# SCH_TSIB_v1_2022-11-26.net
KiCad netlist of a schematic drawn in EasyEDA
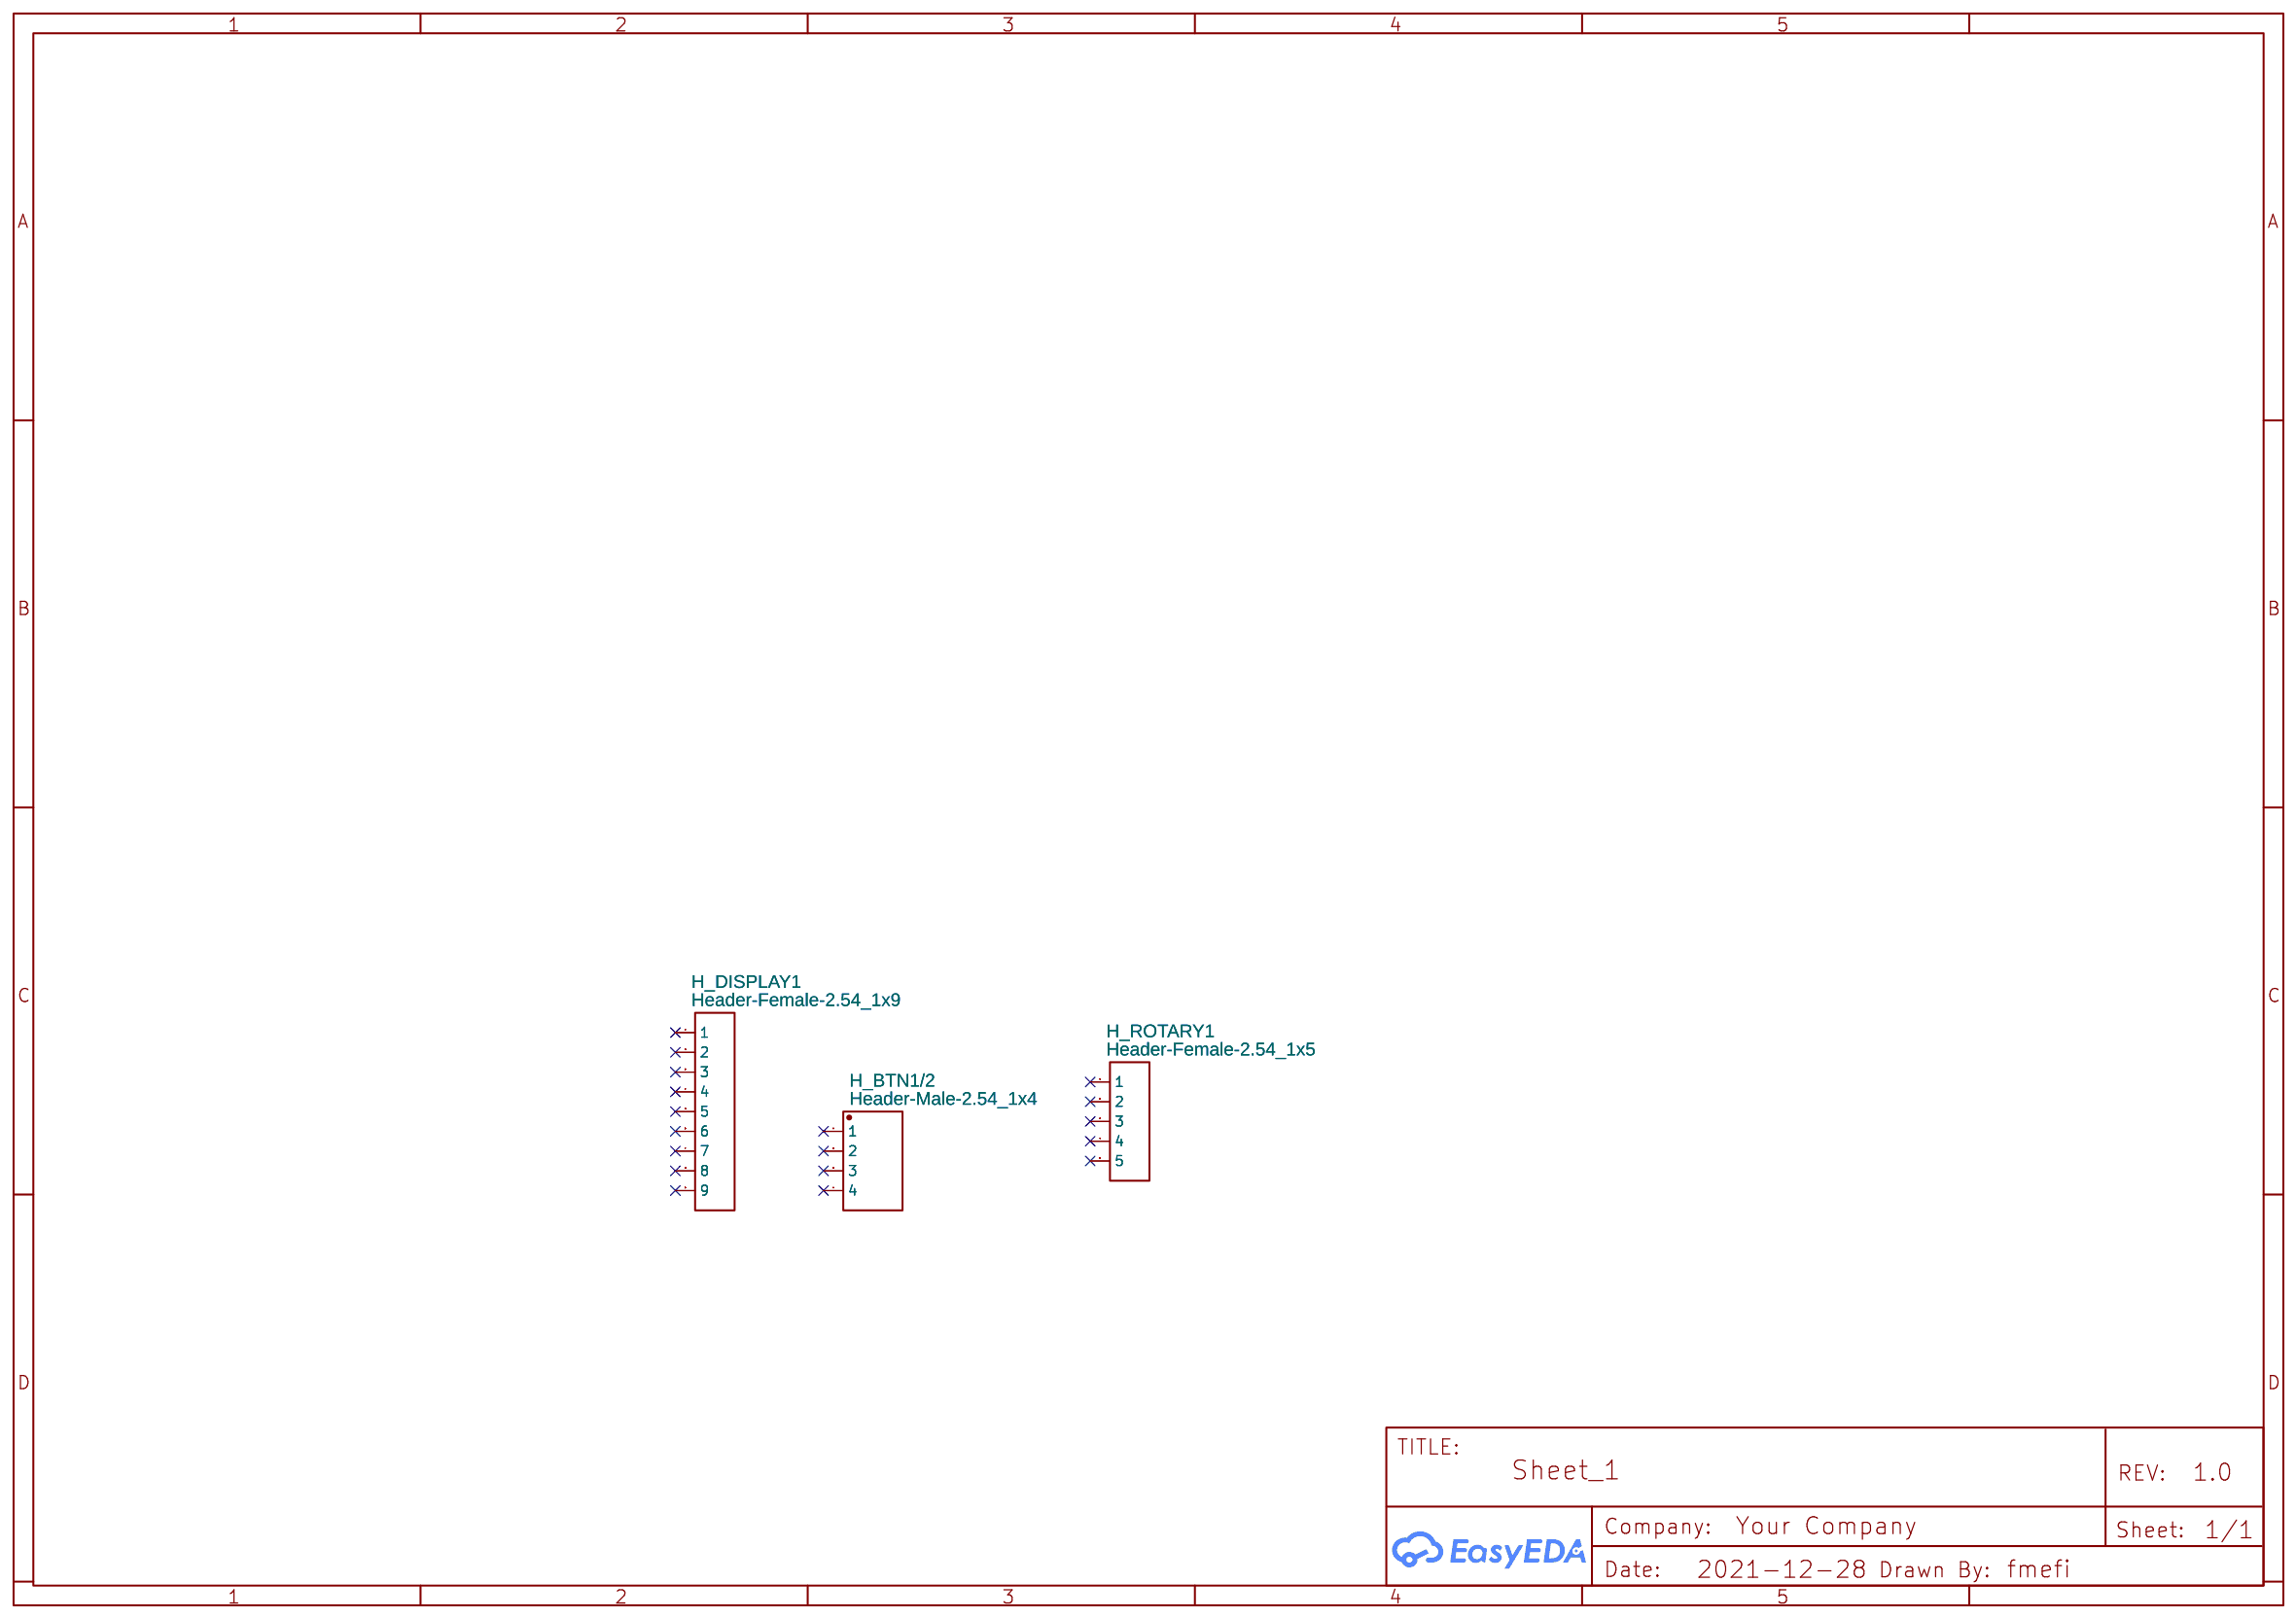
[diagram p0: UX]
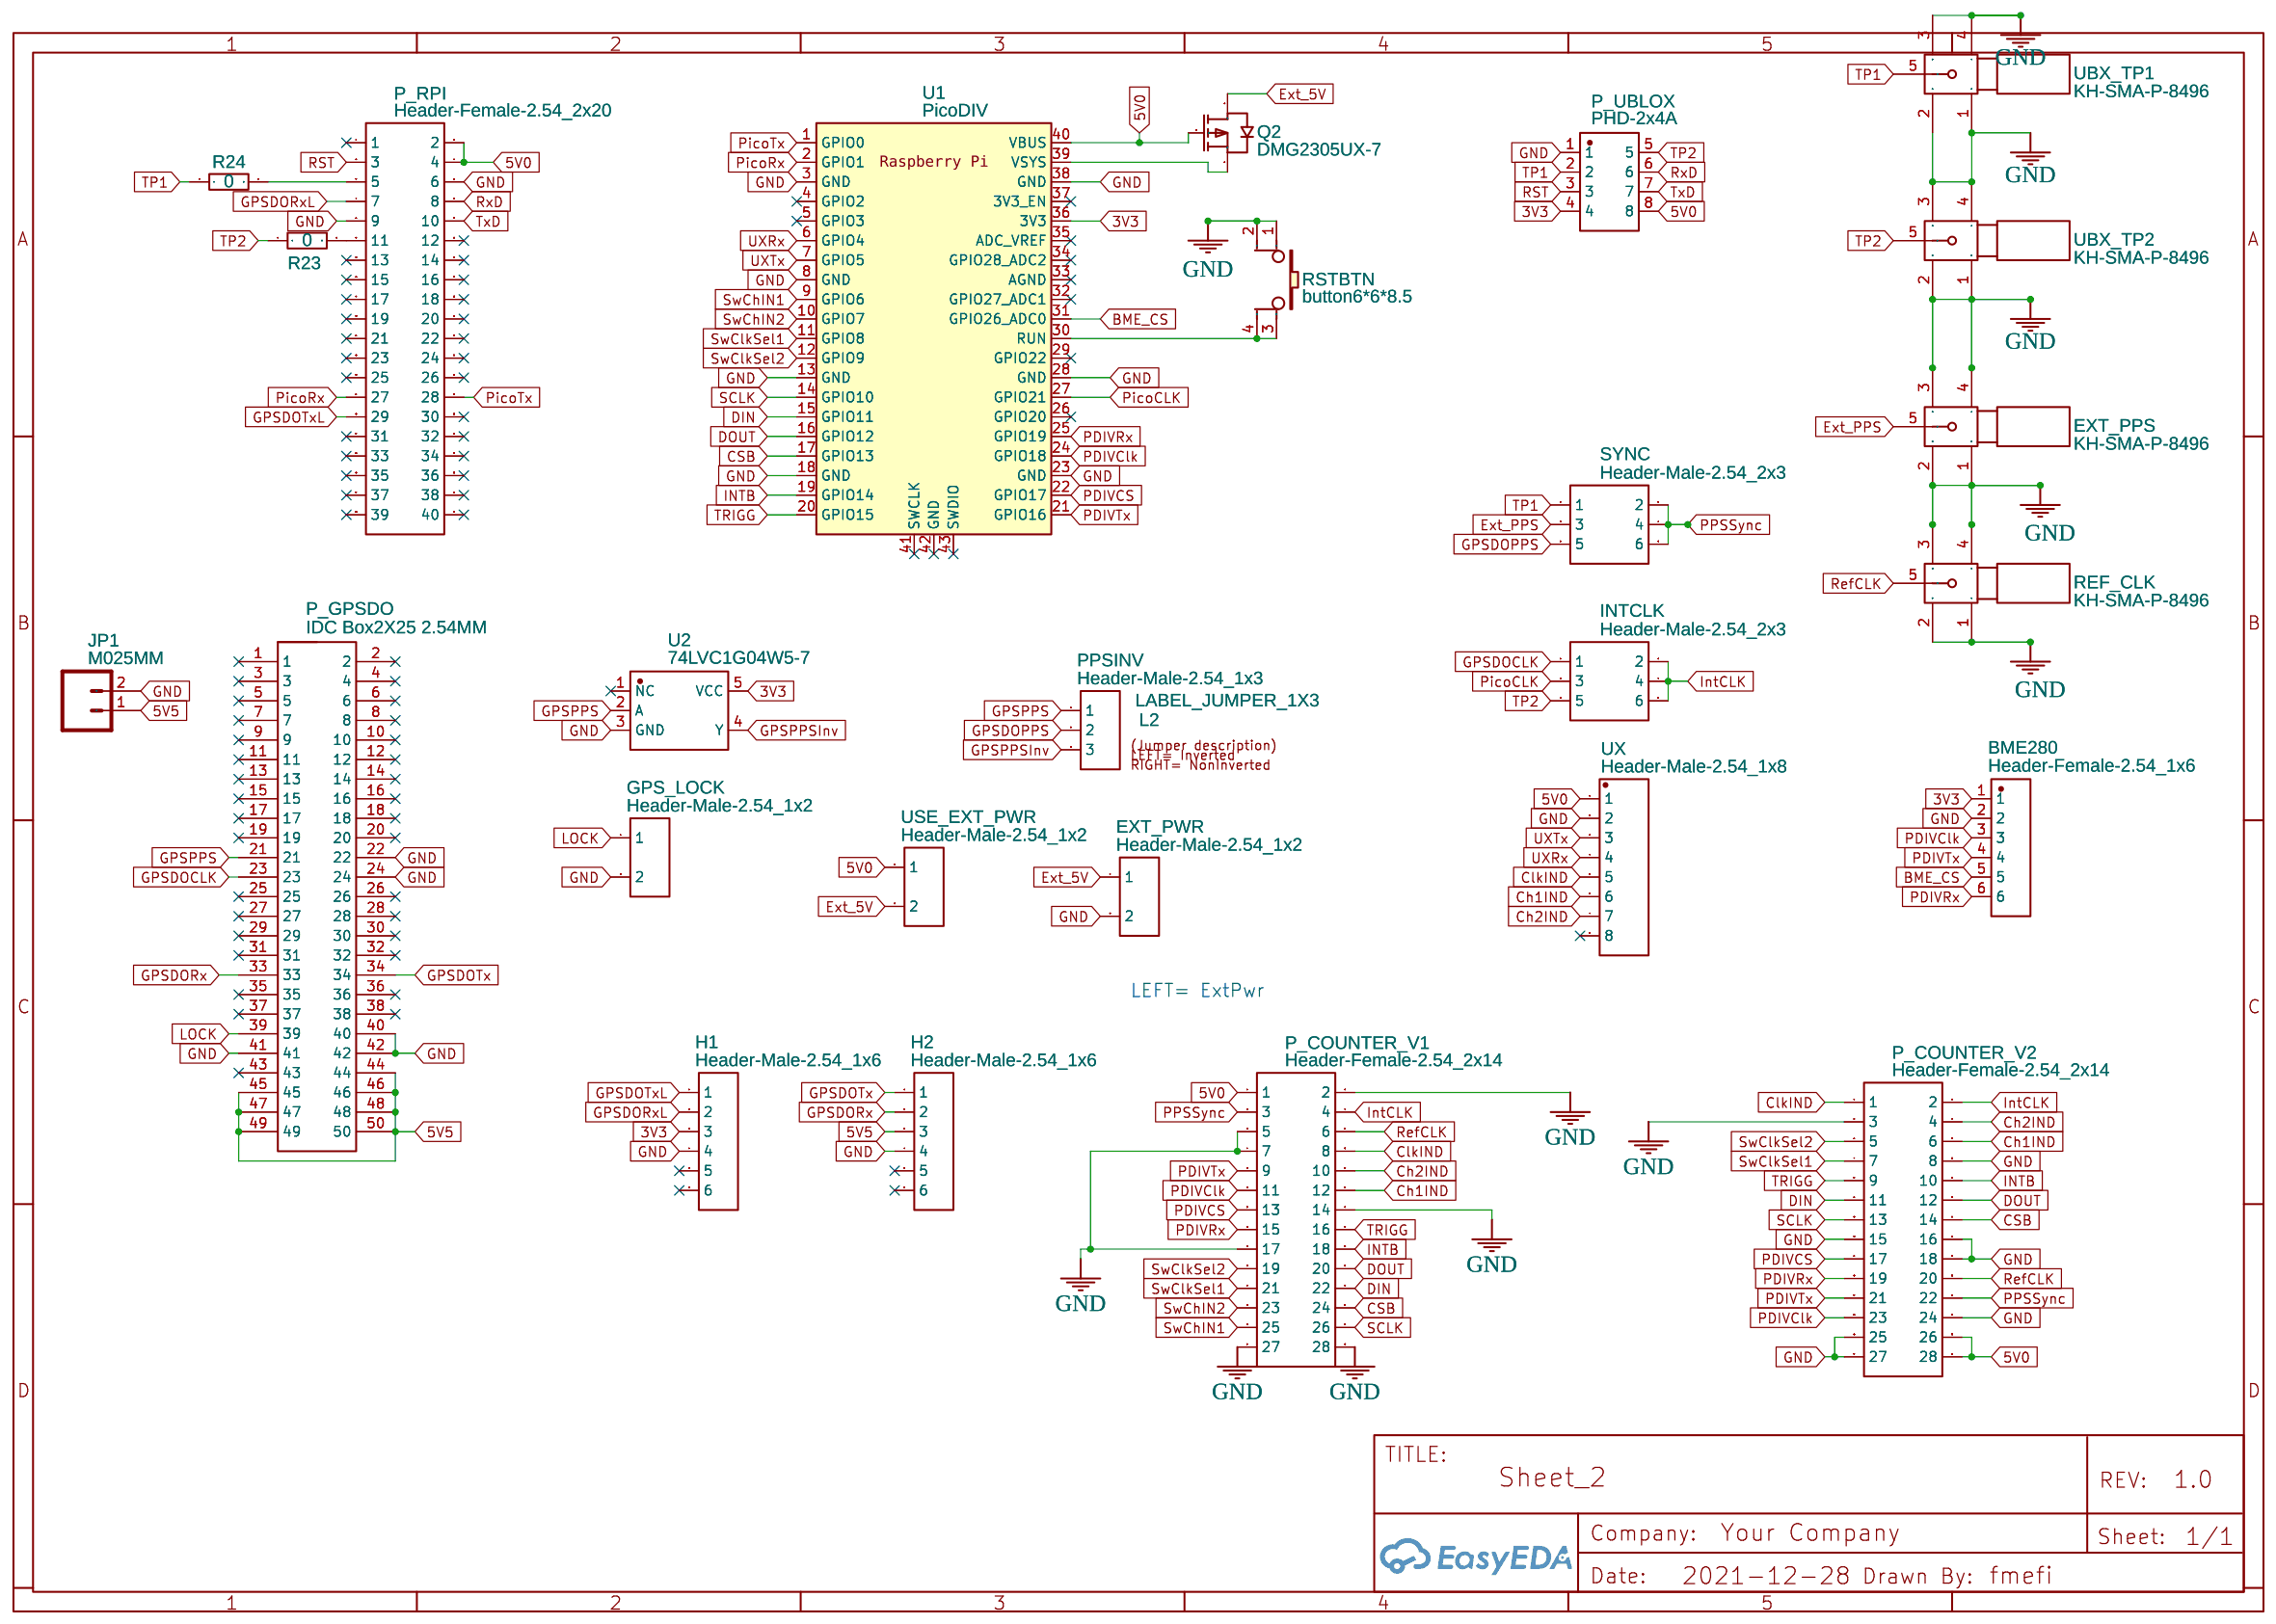
[diagram p1: TSIB_v1.0]

(export (version "E")
  (design (tool "Eeschema 10.0.6"))
  (components
    (comp (ref "H_BTN1/2")
      (value "Header-Male-2.54_1x4")
      (fields
        (field (name "BOM_Manufacturer Part") "210S-1*4P L=11.6MMGold-plated black")
        (field (name "BOM_Supplier Part") "C124378")
      )
      (libsource (lib "") (part "Header-Male-2.54_1x4"))
    )
    (comp (ref "H_DISPLAY1")
      (value "Header-Female-2.54_1x9")
      (fields
        (field (name "BOM_Manufacturer Part") "2.54mm 1*9 Straight Female header")
        (field (name "BOM_Supplier Part") "C39576")
      )
      (libsource (lib "") (part "Header-Female-2.54_1x9"))
    )
    (comp (ref "H_ROTARY1")
      (value "Header-Female-2.54_1x5")
      (fields
        (field (name "BOM_Manufacturer Part") "2.54mm 1*5p Female header")
        (field (name "BOM_Supplier Part") "C50950")
      )
      (libsource (lib "") (part "Header-Female-2.54_1x5"))
    )
    (comp (ref "BME280")
      (value "Header-Female-2.54_1x6")
      (fields
        (field (name "BOM_Manufacturer Part") "Female header 1*6p")
        (field (name "BOM_Supplier Part") "C40877")
      )
      (libsource (lib "") (part "Header-Female-2.54_1x6"))
    )
    (comp (ref "EXT_PPS")
      (value "KH-SMA-P-8496")
      (fields (field (name "BOM_Supplier Part") "C910123"))
      (libsource (lib "") (part "KH-SMA-P-8496_2"))
    )
    (comp (ref "EXT_PWR")
      (value "Header-Male-2.54_1x2")
      (fields (field (name "BOM_Manufacturer Part") "826629-2") (field (name "BOM_Supplier Part") "C86471"))
      (libsource (lib "") (part "Header-Male-2.54_1x2"))
    )
    (comp (ref "GPS_LOCK")
      (value "Header-Male-2.54_1x2")
      (fields (field (name "BOM_Manufacturer Part") "826629-2") (field (name "BOM_Supplier Part") "C86471"))
      (libsource (lib "") (part "Header-Male-2.54_1x2_1"))
    )
    (comp (ref "H1")
      (value "Header-Male-2.54_1x6")
      (fields (field (name "BOM_Supplier Part") "C37208"))
      (libsource (lib "") (part "Header-Male-2.54_1x6"))
    )
    (comp (ref "H2")
      (value "Header-Male-2.54_1x6")
      (fields (field (name "BOM_Supplier Part") "C37208"))
      (libsource (lib "") (part "Header-Male-2.54_1x6"))
    )
    (comp (ref "INTCLK")
      (value "Header-Male-2.54_2x3")
      (fields (field (name "BOM_Supplier Part") "C65114"))
      (libsource (lib "") (part "Header-Male-2.54_2x3_1"))
    )
    (comp (ref "JP1") (value "M025MM") (libsource (lib "") (part "M025MM")))
    (comp (ref "L2") (value "LABEL_JUMPER_1X3") (libsource (lib "") (part "LABEL_JUMPER_1X3")))
    (comp (ref "PPSINV")
      (value "Header-Male-2.54_1x3")
      (fields
        (field (name "BOM_Manufacturer Part") "Header2.54mm 1*3P")
        (field (name "BOM_Supplier Part") "C49257")
      )
      (libsource (lib "") (part "Header-Male-2.54_1x3"))
    )
    (comp (ref "P_COUNTER_V1")
      (value "Header-Female-2.54_2x14")
      (fields
        (field (name "BOM_Manufacturer Part") "2×14 Double female header")
        (field (name "BOM_Supplier Part") "C60375")
      )
      (libsource (lib "") (part "Header-Female-2.54_2x14"))
    )
    (comp (ref "P_COUNTER_V2")
      (value "Header-Female-2.54_2x14")
      (fields
        (field (name "BOM_Manufacturer Part") "2×14 Double female header")
        (field (name "BOM_Supplier Part") "C60375")
      )
      (libsource (lib "") (part "Header-Female-2.54_2x14"))
    )
    (comp (ref "P_GPSDO")
      (value "IDC Box2X25 2.54MM")
      (fields (field (name "BOM_Supplier Part") "C30006"))
      (libsource (lib "") (part "IDC Box2X25 2.54MM"))
    )
    (comp (ref "P_RPI")
      (value "Header-Female-2.54_2x20")
      (fields
        (field (name "BOM_Manufacturer Part") "2.54mm 2*20PFemale header")
        (field (name "BOM_Supplier Part") "C50982")
      )
      (libsource (lib "") (part "Header-Female-2.54_2x20"))
    )
    (comp (ref "P_UBLOX")
      (value "PHD-2x4A")
      (fields
        (field (name "BOM_Manufacturer Part") "PHD2.0mm-2*4header")
        (field (name "BOM_Supplier Part") "C20701")
      )
      (libsource (lib "") (part "PHD-2x4A"))
    )
    (comp (ref "Q2")
      (value "DMG2305UX-7")
      (fields (field (name "BOM_Supplier Part") "C150470"))
      (libsource (lib "") (part "DMG2305UX-7"))
    )
    (comp (ref "R23")
      (value "0")
      (fields
        (field (name "BOM_Manufacturer Part") "0805W8F0000T5E")
        (field (name "BOM_Supplier Part") "C17477")
      )
      (libsource (lib "") (part "0805W8F0000T5E"))
    )
    (comp (ref "R24")
      (value "0")
      (fields
        (field (name "BOM_Manufacturer Part") "0805W8F0000T5E")
        (field (name "BOM_Supplier Part") "C17477")
      )
      (libsource (lib "") (part "0805W8F0000T5E"))
    )
    (comp (ref "REF_CLK")
      (value "KH-SMA-P-8496")
      (fields (field (name "BOM_Supplier Part") "C910123"))
      (libsource (lib "") (part "KH-SMA-P-8496"))
    )
    (comp (ref "RSTBTN")
      (value "button6*6*8.5")
      (fields (field (name "BOM_Supplier Part") "C59980"))
      (libsource (lib "") (part "button6*6*8.5"))
    )
    (comp (ref "SYNC")
      (value "Header-Male-2.54_2x3")
      (fields (field (name "BOM_Supplier Part") "C65114"))
      (libsource (lib "") (part "Header-Male-2.54_2x3"))
    )
    (comp (ref "U1") (value "PicoDIV") (libsource (lib "") (part "Pico")))
    (comp (ref "U2")
      (value "74LVC1G04W5-7")
      (fields (field (name "BOM_Supplier Part") "C460517"))
      (libsource (lib "") (part "74LVC1G04W5-7"))
    )
    (comp (ref "UBX_TP1")
      (value "KH-SMA-P-8496")
      (fields (field (name "BOM_Supplier Part") "C910123"))
      (libsource (lib "") (part "KH-SMA-P-8496_1"))
    )
    (comp (ref "UBX_TP2")
      (value "KH-SMA-P-8496")
      (fields (field (name "BOM_Supplier Part") "C910123"))
      (libsource (lib "") (part "KH-SMA-P-8496_1"))
    )
    (comp (ref "USE_EXT_PWR")
      (value "Header-Male-2.54_1x2")
      (fields (field (name "BOM_Manufacturer Part") "826629-2") (field (name "BOM_Supplier Part") "C86471"))
      (libsource (lib "") (part "Header-Male-2.54_1x2_2"))
    )
    (comp (ref "UX")
      (value "Header-Male-2.54_1x8")
      (fields
        (field (name "BOM_Manufacturer Part") "210S-1*8P L=11.6MMGold-plated black")
        (field (name "BOM_Supplier Part") "C124381")
      )
      (libsource (lib "") (part "Header-Male-2.54_1x8"))
    )
  )
  (nets
    (net (code "1") (name "3V3") (class "Default")
      (node (ref "BME280") (pin "1") (pinfunction "1_1") (pintype "unspecified"))
      (node (ref "H1") (pin "3") (pinfunction "3_3") (pintype "input"))
      (node (ref "P_UBLOX") (pin "4") (pinfunction "4_4") (pintype "unspecified"))
      (node (ref "U1") (pin "36") (pinfunction "3V3_36") (pintype "unspecified"))
      (node (ref "U2") (pin "5") (pinfunction "VCC_5") (pintype "unspecified"))
    )
    (net (code "2") (name "5V0") (class "Default")
      (node (ref "P_COUNTER_V1") (pin "1") (pinfunction "1_1") (pintype "input"))
      (node (ref "P_COUNTER_V2") (pin "26") (pinfunction "26_26") (pintype "input"))
      (node (ref "P_COUNTER_V2") (pin "28") (pinfunction "28_28") (pintype "input"))
      (node (ref "P_RPI") (pin "2") (pinfunction "2_2") (pintype "input"))
      (node (ref "P_RPI") (pin "4") (pinfunction "4_4") (pintype "input"))
      (node (ref "P_UBLOX") (pin "8") (pinfunction "8_8") (pintype "unspecified"))
      (node (ref "Q2") (pin "1") (pinfunction "G_1") (pintype "unspecified"))
      (node (ref "U1") (pin "40") (pinfunction "VBUS_40") (pintype "unspecified"))
      (node (ref "USE_EXT_PWR") (pin "1") (pinfunction "1_1") (pintype "unspecified"))
      (node (ref "UX") (pin "1") (pinfunction "1_1") (pintype "unspecified"))
    )
    (net (code "3") (name "5V5") (class "Default")
      (node (ref "H2") (pin "3") (pinfunction "3_3") (pintype "input"))
      (node (ref "JP1") (pin "1") (pinfunction "1_1") (pintype "unspecified"))
      (node (ref "P_GPSDO") (pin "44") (pinfunction "44_44") (pintype "unspecified"))
      (node (ref "P_GPSDO") (pin "45") (pinfunction "45_45") (pintype "unspecified"))
      (node (ref "P_GPSDO") (pin "46") (pinfunction "46_46") (pintype "unspecified"))
      (node (ref "P_GPSDO") (pin "47") (pinfunction "47_47") (pintype "unspecified"))
      (node (ref "P_GPSDO") (pin "48") (pinfunction "48_48") (pintype "unspecified"))
      (node (ref "P_GPSDO") (pin "49") (pinfunction "49_49") (pintype "unspecified"))
      (node (ref "P_GPSDO") (pin "50") (pinfunction "50_50") (pintype "unspecified"))
    )
    (net (code "4") (name "BME_CS") (class "Default")
      (node (ref "BME280") (pin "5") (pinfunction "5_5") (pintype "unspecified"))
      (node (ref "U1") (pin "31") (pinfunction "GPIO26_ADC0_31") (pintype "bidirectional"))
    )
    (net (code "5") (name "CSB") (class "Default")
      (node (ref "P_COUNTER_V1") (pin "24") (pinfunction "24_24") (pintype "input"))
      (node (ref "P_COUNTER_V2") (pin "14") (pinfunction "14_14") (pintype "input"))
      (node (ref "U1") (pin "17") (pinfunction "GPIO13_17") (pintype "bidirectional"))
    )
    (net (code "6") (name "Ch1IND") (class "Default")
      (node (ref "P_COUNTER_V1") (pin "12") (pinfunction "12_12") (pintype "input"))
      (node (ref "P_COUNTER_V2") (pin "6") (pinfunction "6_6") (pintype "input"))
      (node (ref "UX") (pin "6") (pinfunction "6_6") (pintype "unspecified"))
    )
    (net (code "7") (name "Ch2IND") (class "Default")
      (node (ref "P_COUNTER_V1") (pin "10") (pinfunction "10_10") (pintype "input"))
      (node (ref "P_COUNTER_V2") (pin "4") (pinfunction "4_4") (pintype "input"))
      (node (ref "UX") (pin "7") (pinfunction "7_7") (pintype "unspecified"))
    )
    (net (code "8") (name "ClkIND") (class "Default")
      (node (ref "P_COUNTER_V1") (pin "8") (pinfunction "8_8") (pintype "input"))
      (node (ref "P_COUNTER_V2") (pin "1") (pinfunction "1_1") (pintype "input"))
      (node (ref "UX") (pin "5") (pinfunction "5_5") (pintype "unspecified"))
    )
    (net (code "9") (name "DIN") (class "Default")
      (node (ref "P_COUNTER_V1") (pin "22") (pinfunction "22_22") (pintype "input"))
      (node (ref "P_COUNTER_V2") (pin "11") (pinfunction "11_11") (pintype "input"))
      (node (ref "U1") (pin "15") (pinfunction "GPIO11_15") (pintype "bidirectional"))
    )
    (net (code "10") (name "DOUT") (class "Default")
      (node (ref "P_COUNTER_V1") (pin "20") (pinfunction "20_20") (pintype "input"))
      (node (ref "P_COUNTER_V2") (pin "12") (pinfunction "12_12") (pintype "input"))
      (node (ref "U1") (pin "16") (pinfunction "GPIO12_16") (pintype "bidirectional"))
    )
    (net (code "11") (name "Ext_5V") (class "Default")
      (node (ref "EXT_PWR") (pin "1") (pinfunction "1_1") (pintype "unspecified"))
      (node (ref "Q2") (pin "3") (pinfunction "D_3") (pintype "unspecified"))
      (node (ref "USE_EXT_PWR") (pin "2") (pinfunction "2_2") (pintype "unspecified"))
    )
    (net (code "12") (name "Ext_PPS") (class "Default")
      (node (ref "EXT_PPS") (pin "5") (pinfunction "5_5") (pintype "unspecified"))
      (node (ref "SYNC") (pin "3") (pinfunction "3_3") (pintype "input"))
    )
    (net (code "13") (name "GND") (class "Default")
      (node (ref "BME280") (pin "2") (pinfunction "2_2") (pintype "unspecified"))
      (node (ref "EXT_PPS") (pin "1") (pinfunction "1_1") (pintype "unspecified"))
      (node (ref "EXT_PPS") (pin "2") (pinfunction "2_2") (pintype "unspecified"))
      (node (ref "EXT_PPS") (pin "3") (pinfunction "3_3") (pintype "unspecified"))
      (node (ref "EXT_PPS") (pin "4") (pinfunction "4_4") (pintype "unspecified"))
      (node (ref "EXT_PWR") (pin "2") (pinfunction "2_2") (pintype "unspecified"))
      (node (ref "GPS_LOCK") (pin "2") (pinfunction "2_2") (pintype "unspecified"))
      (node (ref "H1") (pin "4") (pinfunction "4_4") (pintype "input"))
      (node (ref "H2") (pin "4") (pinfunction "4_4") (pintype "input"))
      (node (ref "JP1") (pin "2") (pinfunction "2_2") (pintype "unspecified"))
      (node (ref "P_COUNTER_V1") (pin "14") (pinfunction "14_14") (pintype "input"))
      (node (ref "P_COUNTER_V1") (pin "17") (pinfunction "17_17") (pintype "input"))
      (node (ref "P_COUNTER_V1") (pin "2") (pinfunction "2_2") (pintype "input"))
      (node (ref "P_COUNTER_V1") (pin "27") (pinfunction "27_27") (pintype "input"))
      (node (ref "P_COUNTER_V1") (pin "28") (pinfunction "28_28") (pintype "input"))
      (node (ref "P_COUNTER_V1") (pin "5") (pinfunction "5_5") (pintype "input"))
      (node (ref "P_COUNTER_V1") (pin "7") (pinfunction "7_7") (pintype "input"))
      (node (ref "P_COUNTER_V2") (pin "15") (pinfunction "15_15") (pintype "input"))
      (node (ref "P_COUNTER_V2") (pin "16") (pinfunction "16_16") (pintype "input"))
      (node (ref "P_COUNTER_V2") (pin "18") (pinfunction "18_18") (pintype "input"))
      (node (ref "P_COUNTER_V2") (pin "24") (pinfunction "24_24") (pintype "input"))
      (node (ref "P_COUNTER_V2") (pin "25") (pinfunction "25_25") (pintype "input"))
      (node (ref "P_COUNTER_V2") (pin "27") (pinfunction "27_27") (pintype "input"))
      (node (ref "P_COUNTER_V2") (pin "3") (pinfunction "3_3") (pintype "input"))
      (node (ref "P_COUNTER_V2") (pin "8") (pinfunction "8_8") (pintype "input"))
      (node (ref "P_GPSDO") (pin "22") (pinfunction "22_22") (pintype "unspecified"))
      (node (ref "P_GPSDO") (pin "24") (pinfunction "24_24") (pintype "unspecified"))
      (node (ref "P_GPSDO") (pin "40") (pinfunction "40_40") (pintype "unspecified"))
      (node (ref "P_GPSDO") (pin "41") (pinfunction "41_41") (pintype "unspecified"))
      (node (ref "P_GPSDO") (pin "42") (pinfunction "42_42") (pintype "unspecified"))
      (node (ref "P_RPI") (pin "6") (pinfunction "6_6") (pintype "input"))
      (node (ref "P_RPI") (pin "9") (pinfunction "9_9") (pintype "input"))
      (node (ref "P_UBLOX") (pin "1") (pinfunction "1_1") (pintype "unspecified"))
      (node (ref "REF_CLK") (pin "1") (pinfunction "1_1") (pintype "unspecified"))
      (node (ref "REF_CLK") (pin "2") (pinfunction "2_2") (pintype "unspecified"))
      (node (ref "REF_CLK") (pin "3") (pinfunction "3_3") (pintype "unspecified"))
      (node (ref "REF_CLK") (pin "4") (pinfunction "4_4") (pintype "unspecified"))
      (node (ref "RSTBTN") (pin "1") (pinfunction "1_1") (pintype "input"))
      (node (ref "RSTBTN") (pin "2") (pinfunction "2_2") (pintype "input"))
      (node (ref "U1") (pin "13") (pinfunction "GND_13") (pintype "bidirectional"))
      (node (ref "U1") (pin "18") (pinfunction "GND_18") (pintype "bidirectional"))
      (node (ref "U1") (pin "23") (pinfunction "GND_23") (pintype "bidirectional"))
      (node (ref "U1") (pin "28") (pinfunction "GND_28") (pintype "bidirectional"))
      (node (ref "U1") (pin "3") (pinfunction "GND_3") (pintype "bidirectional"))
      (node (ref "U1") (pin "38") (pinfunction "GND_38") (pintype "bidirectional"))
      (node (ref "U1") (pin "8") (pinfunction "GND_8") (pintype "bidirectional"))
      (node (ref "U2") (pin "3") (pinfunction "GND_3") (pintype "unspecified"))
      (node (ref "UBX_TP1") (pin "1") (pinfunction "1_1") (pintype "unspecified"))
      (node (ref "UBX_TP1") (pin "2") (pinfunction "2_2") (pintype "unspecified"))
      (node (ref "UBX_TP1") (pin "3") (pinfunction "3_3") (pintype "unspecified"))
      (node (ref "UBX_TP1") (pin "4") (pinfunction "4_4") (pintype "unspecified"))
      (node (ref "UBX_TP2") (pin "1") (pinfunction "1_1") (pintype "unspecified"))
      (node (ref "UBX_TP2") (pin "2") (pinfunction "2_2") (pintype "unspecified"))
      (node (ref "UBX_TP2") (pin "3") (pinfunction "3_3") (pintype "unspecified"))
      (node (ref "UBX_TP2") (pin "4") (pinfunction "4_4") (pintype "unspecified"))
      (node (ref "UX") (pin "2") (pinfunction "2_2") (pintype "unspecified"))
    )
    (net (code "14") (name "GPSDOCLK") (class "Default")
      (node (ref "INTCLK") (pin "1") (pinfunction "1_1") (pintype "input"))
      (node (ref "P_GPSDO") (pin "23") (pinfunction "23_23") (pintype "unspecified"))
    )
    (net (code "15") (name "GPSDOPPS") (class "Default")
      (node (ref "PPSINV") (pin "2") (pinfunction "2_2") (pintype "input"))
      (node (ref "SYNC") (pin "5") (pinfunction "5_5") (pintype "input"))
    )
    (net (code "16") (name "GPSDORx") (class "Default")
      (node (ref "H2") (pin "2") (pinfunction "2_2") (pintype "input"))
      (node (ref "P_GPSDO") (pin "33") (pinfunction "33_33") (pintype "unspecified"))
    )
    (net (code "17") (name "GPSDORxL") (class "Default")
      (node (ref "H1") (pin "2") (pinfunction "2_2") (pintype "input"))
      (node (ref "P_RPI") (pin "7") (pinfunction "7_7") (pintype "input"))
    )
    (net (code "18") (name "GPSDOTx") (class "Default")
      (node (ref "H2") (pin "1") (pinfunction "1_1") (pintype "input"))
      (node (ref "P_GPSDO") (pin "34") (pinfunction "34_34") (pintype "unspecified"))
    )
    (net (code "19") (name "GPSDOTxL") (class "Default")
      (node (ref "H1") (pin "1") (pinfunction "1_1") (pintype "input"))
      (node (ref "P_RPI") (pin "29") (pinfunction "29_29") (pintype "input"))
    )
    (net (code "20") (name "GPSPPS") (class "Default")
      (node (ref "PPSINV") (pin "1") (pinfunction "1_1") (pintype "input"))
      (node (ref "P_GPSDO") (pin "21") (pinfunction "21_21") (pintype "unspecified"))
      (node (ref "U2") (pin "2") (pinfunction "A_2") (pintype "unspecified"))
    )
    (net (code "21") (name "GPSPPSInv") (class "Default")
      (node (ref "PPSINV") (pin "3") (pinfunction "3_3") (pintype "input"))
      (node (ref "U2") (pin "4") (pinfunction "Y_4") (pintype "unspecified"))
    )
    (net (code "22") (name "INTB") (class "Default")
      (node (ref "P_COUNTER_V1") (pin "18") (pinfunction "18_18") (pintype "input"))
      (node (ref "P_COUNTER_V2") (pin "10") (pinfunction "10_10") (pintype "input"))
      (node (ref "U1") (pin "19") (pinfunction "GPIO14_19") (pintype "bidirectional"))
    )
    (net (code "23") (name "IntCLK") (class "Default")
      (node (ref "INTCLK") (pin "2") (pinfunction "2_2") (pintype "input"))
      (node (ref "INTCLK") (pin "4") (pinfunction "4_4") (pintype "input"))
      (node (ref "INTCLK") (pin "6") (pinfunction "6_6") (pintype "input"))
      (node (ref "P_COUNTER_V1") (pin "4") (pinfunction "4_4") (pintype "input"))
      (node (ref "P_COUNTER_V2") (pin "2") (pinfunction "2_2") (pintype "input"))
    )
    (net (code "24") (name "LOCK") (class "Default")
      (node (ref "GPS_LOCK") (pin "1") (pinfunction "1_1") (pintype "unspecified"))
      (node (ref "P_GPSDO") (pin "39") (pinfunction "39_39") (pintype "unspecified"))
    )
    (net (code "25") (name "Net-(P_RPI-Pad5)") (class "Default")
      (node (ref "P_RPI") (pin "5") (pinfunction "5_5") (pintype "input"))
      (node (ref "R24") (pin "2") (pinfunction "2_2") (pintype "input"))
    )
    (net (code "26") (name "Net-(P_RPI-Pad11)") (class "Default")
      (node (ref "P_RPI") (pin "11") (pinfunction "11_11") (pintype "input"))
      (node (ref "R23") (pin "2") (pinfunction "2_2") (pintype "input"))
    )
    (net (code "27") (name "Net-(Q2-S)") (class "Default")
      (node (ref "Q2") (pin "2") (pinfunction "S_2") (pintype "unspecified"))
      (node (ref "U1") (pin "39") (pinfunction "VSYS_39") (pintype "unspecified"))
    )
    (net (code "28") (name "Net-(U1-RUN)") (class "Default")
      (node (ref "RSTBTN") (pin "3") (pinfunction "3_3") (pintype "input"))
      (node (ref "RSTBTN") (pin "4") (pinfunction "4_4") (pintype "input"))
      (node (ref "U1") (pin "30") (pinfunction "RUN_30") (pintype "input"))
    )
    (net (code "29") (name "PDIVCS") (class "Default")
      (node (ref "P_COUNTER_V1") (pin "13") (pinfunction "13_13") (pintype "input"))
      (node (ref "P_COUNTER_V2") (pin "17") (pinfunction "17_17") (pintype "input"))
      (node (ref "U1") (pin "22") (pinfunction "GPIO17_22") (pintype "bidirectional"))
    )
    (net (code "30") (name "PDIVClk") (class "Default")
      (node (ref "BME280") (pin "3") (pinfunction "3_3") (pintype "unspecified"))
      (node (ref "P_COUNTER_V1") (pin "11") (pinfunction "11_11") (pintype "input"))
      (node (ref "P_COUNTER_V2") (pin "23") (pinfunction "23_23") (pintype "input"))
      (node (ref "U1") (pin "24") (pinfunction "GPIO18_24") (pintype "bidirectional"))
    )
    (net (code "31") (name "PDIVRx") (class "Default")
      (node (ref "BME280") (pin "6") (pinfunction "6_6") (pintype "unspecified"))
      (node (ref "P_COUNTER_V1") (pin "15") (pinfunction "15_15") (pintype "input"))
      (node (ref "P_COUNTER_V2") (pin "19") (pinfunction "19_19") (pintype "input"))
      (node (ref "U1") (pin "25") (pinfunction "GPIO19_25") (pintype "bidirectional"))
    )
    (net (code "32") (name "PDIVTx") (class "Default")
      (node (ref "BME280") (pin "4") (pinfunction "4_4") (pintype "unspecified"))
      (node (ref "P_COUNTER_V1") (pin "9") (pinfunction "9_9") (pintype "input"))
      (node (ref "P_COUNTER_V2") (pin "21") (pinfunction "21_21") (pintype "input"))
      (node (ref "U1") (pin "21") (pinfunction "GPIO16_21") (pintype "bidirectional"))
    )
    (net (code "33") (name "PPSSync") (class "Default")
      (node (ref "P_COUNTER_V1") (pin "3") (pinfunction "3_3") (pintype "input"))
      (node (ref "P_COUNTER_V2") (pin "22") (pinfunction "22_22") (pintype "input"))
      (node (ref "SYNC") (pin "2") (pinfunction "2_2") (pintype "input"))
      (node (ref "SYNC") (pin "4") (pinfunction "4_4") (pintype "input"))
      (node (ref "SYNC") (pin "6") (pinfunction "6_6") (pintype "input"))
    )
    (net (code "34") (name "PicoCLK") (class "Default")
      (node (ref "INTCLK") (pin "3") (pinfunction "3_3") (pintype "input"))
      (node (ref "U1") (pin "27") (pinfunction "GPIO21_27") (pintype "bidirectional"))
    )
    (net (code "35") (name "PicoRx") (class "Default")
      (node (ref "P_RPI") (pin "27") (pinfunction "27_27") (pintype "input"))
      (node (ref "U1") (pin "2") (pinfunction "GPIO1_2") (pintype "bidirectional"))
    )
    (net (code "36") (name "PicoTx") (class "Default")
      (node (ref "P_RPI") (pin "28") (pinfunction "28_28") (pintype "input"))
      (node (ref "U1") (pin "1") (pinfunction "GPIO0_1") (pintype "bidirectional"))
    )
    (net (code "37") (name "RST") (class "Default")
      (node (ref "P_RPI") (pin "3") (pinfunction "3_3") (pintype "input"))
      (node (ref "P_UBLOX") (pin "3") (pinfunction "3_3") (pintype "unspecified"))
    )
    (net (code "38") (name "RefCLK") (class "Default")
      (node (ref "P_COUNTER_V1") (pin "6") (pinfunction "6_6") (pintype "input"))
      (node (ref "P_COUNTER_V2") (pin "20") (pinfunction "20_20") (pintype "input"))
      (node (ref "REF_CLK") (pin "5") (pinfunction "5_5") (pintype "unspecified"))
    )
    (net (code "39") (name "RxD") (class "Default")
      (node (ref "P_RPI") (pin "8") (pinfunction "8_8") (pintype "input"))
      (node (ref "P_UBLOX") (pin "6") (pinfunction "6_6") (pintype "unspecified"))
    )
    (net (code "40") (name "SCLK") (class "Default")
      (node (ref "P_COUNTER_V1") (pin "26") (pinfunction "26_26") (pintype "input"))
      (node (ref "P_COUNTER_V2") (pin "13") (pinfunction "13_13") (pintype "input"))
      (node (ref "U1") (pin "14") (pinfunction "GPIO10_14") (pintype "bidirectional"))
    )
    (net (code "41") (name "SwChIN1") (class "Default")
      (node (ref "P_COUNTER_V1") (pin "25") (pinfunction "25_25") (pintype "input"))
      (node (ref "U1") (pin "9") (pinfunction "GPIO6_9") (pintype "bidirectional"))
    )
    (net (code "42") (name "SwChIN2") (class "Default")
      (node (ref "P_COUNTER_V1") (pin "23") (pinfunction "23_23") (pintype "input"))
      (node (ref "U1") (pin "10") (pinfunction "GPIO7_10") (pintype "bidirectional"))
    )
    (net (code "43") (name "SwClkSel1") (class "Default")
      (node (ref "P_COUNTER_V1") (pin "21") (pinfunction "21_21") (pintype "input"))
      (node (ref "P_COUNTER_V2") (pin "7") (pinfunction "7_7") (pintype "input"))
      (node (ref "U1") (pin "11") (pinfunction "GPIO8_11") (pintype "bidirectional"))
    )
    (net (code "44") (name "SwClkSel2") (class "Default")
      (node (ref "P_COUNTER_V1") (pin "19") (pinfunction "19_19") (pintype "input"))
      (node (ref "P_COUNTER_V2") (pin "5") (pinfunction "5_5") (pintype "input"))
      (node (ref "U1") (pin "12") (pinfunction "GPIO9_12") (pintype "bidirectional"))
    )
    (net (code "45") (name "TP1") (class "Default")
      (node (ref "P_UBLOX") (pin "2") (pinfunction "2_2") (pintype "unspecified"))
      (node (ref "R24") (pin "1") (pinfunction "1_1") (pintype "input"))
      (node (ref "SYNC") (pin "1") (pinfunction "1_1") (pintype "input"))
      (node (ref "UBX_TP1") (pin "5") (pinfunction "5_5") (pintype "unspecified"))
    )
    (net (code "46") (name "TP2") (class "Default")
      (node (ref "INTCLK") (pin "5") (pinfunction "5_5") (pintype "input"))
      (node (ref "P_UBLOX") (pin "5") (pinfunction "5_5") (pintype "unspecified"))
      (node (ref "R23") (pin "1") (pinfunction "1_1") (pintype "input"))
      (node (ref "UBX_TP2") (pin "5") (pinfunction "5_5") (pintype "unspecified"))
    )
    (net (code "47") (name "TRIGG") (class "Default")
      (node (ref "P_COUNTER_V1") (pin "16") (pinfunction "16_16") (pintype "input"))
      (node (ref "P_COUNTER_V2") (pin "9") (pinfunction "9_9") (pintype "input"))
      (node (ref "U1") (pin "20") (pinfunction "GPIO15_20") (pintype "bidirectional"))
    )
    (net (code "48") (name "TxD") (class "Default")
      (node (ref "P_RPI") (pin "10") (pinfunction "10_10") (pintype "input"))
      (node (ref "P_UBLOX") (pin "7") (pinfunction "7_7") (pintype "unspecified"))
    )
    (net (code "49") (name "UXRx") (class "Default")
      (node (ref "U1") (pin "6") (pinfunction "GPIO4_6") (pintype "bidirectional"))
      (node (ref "UX") (pin "4") (pinfunction "4_4") (pintype "unspecified"))
    )
    (net (code "50") (name "UXTx") (class "Default")
      (node (ref "U1") (pin "7") (pinfunction "GPIO5_7") (pintype "bidirectional"))
      (node (ref "UX") (pin "3") (pinfunction "3_3") (pintype "unspecified"))
    )
    (net (code "51") (name "unconnected-(H1-Pad5)") (class "Default")
      (node (ref "H1") (pin "5") (pinfunction "5_5") (pintype "input+no_connect"))
    )
    (net (code "52") (name "unconnected-(H1-Pad6)") (class "Default")
      (node (ref "H1") (pin "6") (pinfunction "6_6") (pintype "input+no_connect"))
    )
    (net (code "53") (name "unconnected-(H2-Pad5)") (class "Default")
      (node (ref "H2") (pin "5") (pinfunction "5_5") (pintype "input+no_connect"))
    )
    (net (code "54") (name "unconnected-(H2-Pad6)") (class "Default")
      (node (ref "H2") (pin "6") (pinfunction "6_6") (pintype "input+no_connect"))
    )
    (net (code "55") (name "unconnected-(H_BTN1/2-Pad1)") (class "Default")
      (node (ref "H_BTN1/2") (pin "1") (pinfunction "1_1") (pintype "unspecified+no_connect"))
    )
    (net (code "56") (name "unconnected-(H_BTN1/2-Pad2)") (class "Default")
      (node (ref "H_BTN1/2") (pin "2") (pinfunction "2_2") (pintype "unspecified+no_connect"))
    )
    (net (code "57") (name "unconnected-(H_BTN1/2-Pad3)") (class "Default")
      (node (ref "H_BTN1/2") (pin "3") (pinfunction "3_3") (pintype "unspecified+no_connect"))
    )
    (net (code "58") (name "unconnected-(H_BTN1/2-Pad4)") (class "Default")
      (node (ref "H_BTN1/2") (pin "4") (pinfunction "4_4") (pintype "unspecified+no_connect"))
    )
    (net (code "59") (name "unconnected-(H_DISPLAY1-Pad1)") (class "Default")
      (node (ref "H_DISPLAY1") (pin "1") (pinfunction "1_1") (pintype "input+no_connect"))
    )
    (net (code "60") (name "unconnected-(H_DISPLAY1-Pad2)") (class "Default")
      (node (ref "H_DISPLAY1") (pin "2") (pinfunction "2_2") (pintype "input+no_connect"))
    )
    (net (code "61") (name "unconnected-(H_DISPLAY1-Pad3)") (class "Default")
      (node (ref "H_DISPLAY1") (pin "3") (pinfunction "3_3") (pintype "input+no_connect"))
    )
    (net (code "62") (name "unconnected-(H_DISPLAY1-Pad4)") (class "Default")
      (node (ref "H_DISPLAY1") (pin "4") (pinfunction "4_4") (pintype "input+no_connect"))
    )
    (net (code "63") (name "unconnected-(H_DISPLAY1-Pad5)") (class "Default")
      (node (ref "H_DISPLAY1") (pin "5") (pinfunction "5_5") (pintype "input+no_connect"))
    )
    (net (code "64") (name "unconnected-(H_DISPLAY1-Pad6)") (class "Default")
      (node (ref "H_DISPLAY1") (pin "6") (pinfunction "6_6") (pintype "input+no_connect"))
    )
    (net (code "65") (name "unconnected-(H_DISPLAY1-Pad7)") (class "Default")
      (node (ref "H_DISPLAY1") (pin "7") (pinfunction "7_7") (pintype "input+no_connect"))
    )
    (net (code "66") (name "unconnected-(H_DISPLAY1-Pad8)") (class "Default")
      (node (ref "H_DISPLAY1") (pin "8") (pinfunction "8_8") (pintype "input+no_connect"))
    )
    (net (code "67") (name "unconnected-(H_DISPLAY1-Pad9)") (class "Default")
      (node (ref "H_DISPLAY1") (pin "9") (pinfunction "9_9") (pintype "input+no_connect"))
    )
    (net (code "68") (name "unconnected-(H_ROTARY1-Pad1)") (class "Default")
      (node (ref "H_ROTARY1") (pin "1") (pinfunction "1_1") (pintype "input+no_connect"))
    )
    (net (code "69") (name "unconnected-(H_ROTARY1-Pad2)") (class "Default")
      (node (ref "H_ROTARY1") (pin "2") (pinfunction "2_2") (pintype "input+no_connect"))
    )
    (net (code "70") (name "unconnected-(H_ROTARY1-Pad3)") (class "Default")
      (node (ref "H_ROTARY1") (pin "3") (pinfunction "3_3") (pintype "input+no_connect"))
    )
    (net (code "71") (name "unconnected-(H_ROTARY1-Pad4)") (class "Default")
      (node (ref "H_ROTARY1") (pin "4") (pinfunction "4_4") (pintype "input+no_connect"))
    )
    (net (code "72") (name "unconnected-(H_ROTARY1-Pad5)") (class "Default")
      (node (ref "H_ROTARY1") (pin "5") (pinfunction "5_5") (pintype "input+no_connect"))
    )
    (net (code "73") (name "unconnected-(P_GPSDO-Pad1)") (class "Default")
      (node (ref "P_GPSDO") (pin "1") (pinfunction "1_1") (pintype "unspecified+no_connect"))
    )
    (net (code "74") (name "unconnected-(P_GPSDO-Pad2)") (class "Default")
      (node (ref "P_GPSDO") (pin "2") (pinfunction "2_2") (pintype "unspecified+no_connect"))
    )
    (net (code "75") (name "unconnected-(P_GPSDO-Pad3)") (class "Default")
      (node (ref "P_GPSDO") (pin "3") (pinfunction "3_3") (pintype "unspecified+no_connect"))
    )
    (net (code "76") (name "unconnected-(P_GPSDO-Pad4)") (class "Default")
      (node (ref "P_GPSDO") (pin "4") (pinfunction "4_4") (pintype "unspecified+no_connect"))
    )
    (net (code "77") (name "unconnected-(P_GPSDO-Pad5)") (class "Default")
      (node (ref "P_GPSDO") (pin "5") (pinfunction "5_5") (pintype "unspecified+no_connect"))
    )
    (net (code "78") (name "unconnected-(P_GPSDO-Pad6)") (class "Default")
      (node (ref "P_GPSDO") (pin "6") (pinfunction "6_6") (pintype "unspecified+no_connect"))
    )
    (net (code "79") (name "unconnected-(P_GPSDO-Pad7)") (class "Default")
      (node (ref "P_GPSDO") (pin "7") (pinfunction "7_7") (pintype "unspecified+no_connect"))
    )
    (net (code "80") (name "unconnected-(P_GPSDO-Pad8)") (class "Default")
      (node (ref "P_GPSDO") (pin "8") (pinfunction "8_8") (pintype "unspecified+no_connect"))
    )
    (net (code "81") (name "unconnected-(P_GPSDO-Pad9)") (class "Default")
      (node (ref "P_GPSDO") (pin "9") (pinfunction "9_9") (pintype "unspecified+no_connect"))
    )
    (net (code "82") (name "unconnected-(P_GPSDO-Pad10)") (class "Default")
      (node (ref "P_GPSDO") (pin "10") (pinfunction "10_10") (pintype "unspecified+no_connect"))
    )
    (net (code "83") (name "unconnected-(P_GPSDO-Pad11)") (class "Default")
      (node (ref "P_GPSDO") (pin "11") (pinfunction "11_11") (pintype "unspecified+no_connect"))
    )
    (net (code "84") (name "unconnected-(P_GPSDO-Pad12)") (class "Default")
      (node (ref "P_GPSDO") (pin "12") (pinfunction "12_12") (pintype "unspecified+no_connect"))
    )
    (net (code "85") (name "unconnected-(P_GPSDO-Pad13)") (class "Default")
      (node (ref "P_GPSDO") (pin "13") (pinfunction "13_13") (pintype "unspecified+no_connect"))
    )
    (net (code "86") (name "unconnected-(P_GPSDO-Pad14)") (class "Default")
      (node (ref "P_GPSDO") (pin "14") (pinfunction "14_14") (pintype "unspecified+no_connect"))
    )
    (net (code "87") (name "unconnected-(P_GPSDO-Pad15)") (class "Default")
      (node (ref "P_GPSDO") (pin "15") (pinfunction "15_15") (pintype "unspecified+no_connect"))
    )
    (net (code "88") (name "unconnected-(P_GPSDO-Pad16)") (class "Default")
      (node (ref "P_GPSDO") (pin "16") (pinfunction "16_16") (pintype "unspecified+no_connect"))
    )
    (net (code "89") (name "unconnected-(P_GPSDO-Pad17)") (class "Default")
      (node (ref "P_GPSDO") (pin "17") (pinfunction "17_17") (pintype "unspecified+no_connect"))
    )
    (net (code "90") (name "unconnected-(P_GPSDO-Pad18)") (class "Default")
      (node (ref "P_GPSDO") (pin "18") (pinfunction "18_18") (pintype "unspecified+no_connect"))
    )
    (net (code "91") (name "unconnected-(P_GPSDO-Pad19)") (class "Default")
      (node (ref "P_GPSDO") (pin "19") (pinfunction "19_19") (pintype "unspecified+no_connect"))
    )
    (net (code "92") (name "unconnected-(P_GPSDO-Pad20)") (class "Default")
      (node (ref "P_GPSDO") (pin "20") (pinfunction "20_20") (pintype "unspecified+no_connect"))
    )
    (net (code "93") (name "unconnected-(P_GPSDO-Pad25)") (class "Default")
      (node (ref "P_GPSDO") (pin "25") (pinfunction "25_25") (pintype "unspecified+no_connect"))
    )
    (net (code "94") (name "unconnected-(P_GPSDO-Pad26)") (class "Default")
      (node (ref "P_GPSDO") (pin "26") (pinfunction "26_26") (pintype "unspecified+no_connect"))
    )
    (net (code "95") (name "unconnected-(P_GPSDO-Pad27)") (class "Default")
      (node (ref "P_GPSDO") (pin "27") (pinfunction "27_27") (pintype "unspecified+no_connect"))
    )
    (net (code "96") (name "unconnected-(P_GPSDO-Pad28)") (class "Default")
      (node (ref "P_GPSDO") (pin "28") (pinfunction "28_28") (pintype "unspecified+no_connect"))
    )
    (net (code "97") (name "unconnected-(P_GPSDO-Pad29)") (class "Default")
      (node (ref "P_GPSDO") (pin "29") (pinfunction "29_29") (pintype "unspecified+no_connect"))
    )
    (net (code "98") (name "unconnected-(P_GPSDO-Pad30)") (class "Default")
      (node (ref "P_GPSDO") (pin "30") (pinfunction "30_30") (pintype "unspecified+no_connect"))
    )
    (net (code "99") (name "unconnected-(P_GPSDO-Pad31)") (class "Default")
      (node (ref "P_GPSDO") (pin "31") (pinfunction "31_31") (pintype "unspecified+no_connect"))
    )
    (net (code "100") (name "unconnected-(P_GPSDO-Pad32)") (class "Default")
      (node (ref "P_GPSDO") (pin "32") (pinfunction "32_32") (pintype "unspecified+no_connect"))
    )
    (net (code "101") (name "unconnected-(P_GPSDO-Pad35)") (class "Default")
      (node (ref "P_GPSDO") (pin "35") (pinfunction "35_35") (pintype "unspecified+no_connect"))
    )
    (net (code "102") (name "unconnected-(P_GPSDO-Pad36)") (class "Default")
      (node (ref "P_GPSDO") (pin "36") (pinfunction "36_36") (pintype "unspecified+no_connect"))
    )
    (net (code "103") (name "unconnected-(P_GPSDO-Pad37)") (class "Default")
      (node (ref "P_GPSDO") (pin "37") (pinfunction "37_37") (pintype "unspecified+no_connect"))
    )
    (net (code "104") (name "unconnected-(P_GPSDO-Pad38)") (class "Default")
      (node (ref "P_GPSDO") (pin "38") (pinfunction "38_38") (pintype "unspecified+no_connect"))
    )
    (net (code "105") (name "unconnected-(P_GPSDO-Pad43)") (class "Default")
      (node (ref "P_GPSDO") (pin "43") (pinfunction "43_43") (pintype "unspecified+no_connect"))
    )
    (net (code "106") (name "unconnected-(P_RPI-Pad1)") (class "Default")
      (node (ref "P_RPI") (pin "1") (pinfunction "1_1") (pintype "input+no_connect"))
    )
    (net (code "107") (name "unconnected-(P_RPI-Pad12)") (class "Default")
      (node (ref "P_RPI") (pin "12") (pinfunction "12_12") (pintype "input+no_connect"))
    )
    (net (code "108") (name "unconnected-(P_RPI-Pad13)") (class "Default")
      (node (ref "P_RPI") (pin "13") (pinfunction "13_13") (pintype "input+no_connect"))
    )
    (net (code "109") (name "unconnected-(P_RPI-Pad14)") (class "Default")
      (node (ref "P_RPI") (pin "14") (pinfunction "14_14") (pintype "input+no_connect"))
    )
    (net (code "110") (name "unconnected-(P_RPI-Pad15)") (class "Default")
      (node (ref "P_RPI") (pin "15") (pinfunction "15_15") (pintype "input+no_connect"))
    )
    (net (code "111") (name "unconnected-(P_RPI-Pad16)") (class "Default")
      (node (ref "P_RPI") (pin "16") (pinfunction "16_16") (pintype "input+no_connect"))
    )
    (net (code "112") (name "unconnected-(P_RPI-Pad17)") (class "Default")
      (node (ref "P_RPI") (pin "17") (pinfunction "17_17") (pintype "input+no_connect"))
    )
    (net (code "113") (name "unconnected-(P_RPI-Pad18)") (class "Default")
      (node (ref "P_RPI") (pin "18") (pinfunction "18_18") (pintype "input+no_connect"))
    )
    (net (code "114") (name "unconnected-(P_RPI-Pad19)") (class "Default")
      (node (ref "P_RPI") (pin "19") (pinfunction "19_19") (pintype "input+no_connect"))
    )
    (net (code "115") (name "unconnected-(P_RPI-Pad20)") (class "Default")
      (node (ref "P_RPI") (pin "20") (pinfunction "20_20") (pintype "input+no_connect"))
    )
    (net (code "116") (name "unconnected-(P_RPI-Pad21)") (class "Default")
      (node (ref "P_RPI") (pin "21") (pinfunction "21_21") (pintype "input+no_connect"))
    )
    (net (code "117") (name "unconnected-(P_RPI-Pad22)") (class "Default")
      (node (ref "P_RPI") (pin "22") (pinfunction "22_22") (pintype "input+no_connect"))
    )
    (net (code "118") (name "unconnected-(P_RPI-Pad23)") (class "Default")
      (node (ref "P_RPI") (pin "23") (pinfunction "23_23") (pintype "input+no_connect"))
    )
    (net (code "119") (name "unconnected-(P_RPI-Pad24)") (class "Default")
      (node (ref "P_RPI") (pin "24") (pinfunction "24_24") (pintype "input+no_connect"))
    )
    (net (code "120") (name "unconnected-(P_RPI-Pad25)") (class "Default")
      (node (ref "P_RPI") (pin "25") (pinfunction "25_25") (pintype "input+no_connect"))
    )
    (net (code "121") (name "unconnected-(P_RPI-Pad26)") (class "Default")
      (node (ref "P_RPI") (pin "26") (pinfunction "26_26") (pintype "input+no_connect"))
    )
    (net (code "122") (name "unconnected-(P_RPI-Pad30)") (class "Default")
      (node (ref "P_RPI") (pin "30") (pinfunction "30_30") (pintype "input+no_connect"))
    )
    (net (code "123") (name "unconnected-(P_RPI-Pad31)") (class "Default")
      (node (ref "P_RPI") (pin "31") (pinfunction "31_31") (pintype "input+no_connect"))
    )
    (net (code "124") (name "unconnected-(P_RPI-Pad32)") (class "Default")
      (node (ref "P_RPI") (pin "32") (pinfunction "32_32") (pintype "input+no_connect"))
    )
    (net (code "125") (name "unconnected-(P_RPI-Pad33)") (class "Default")
      (node (ref "P_RPI") (pin "33") (pinfunction "33_33") (pintype "input+no_connect"))
    )
    (net (code "126") (name "unconnected-(P_RPI-Pad34)") (class "Default")
      (node (ref "P_RPI") (pin "34") (pinfunction "34_34") (pintype "input+no_connect"))
    )
    (net (code "127") (name "unconnected-(P_RPI-Pad35)") (class "Default")
      (node (ref "P_RPI") (pin "35") (pinfunction "35_35") (pintype "input+no_connect"))
    )
    (net (code "128") (name "unconnected-(P_RPI-Pad36)") (class "Default")
      (node (ref "P_RPI") (pin "36") (pinfunction "36_36") (pintype "input+no_connect"))
    )
    (net (code "129") (name "unconnected-(P_RPI-Pad37)") (class "Default")
      (node (ref "P_RPI") (pin "37") (pinfunction "37_37") (pintype "input+no_connect"))
    )
    (net (code "130") (name "unconnected-(P_RPI-Pad38)") (class "Default")
      (node (ref "P_RPI") (pin "38") (pinfunction "38_38") (pintype "input+no_connect"))
    )
    (net (code "131") (name "unconnected-(P_RPI-Pad39)") (class "Default")
      (node (ref "P_RPI") (pin "39") (pinfunction "39_39") (pintype "input+no_connect"))
    )
    (net (code "132") (name "unconnected-(P_RPI-Pad40)") (class "Default")
      (node (ref "P_RPI") (pin "40") (pinfunction "40_40") (pintype "input+no_connect"))
    )
    (net (code "133") (name "unconnected-(U1-3V3_EN-Pad37)") (class "Default")
      (node (ref "U1") (pin "37") (pinfunction "3V3_EN_37") (pintype "input+no_connect"))
    )
    (net (code "134") (name "unconnected-(U1-ADC_VREF-Pad35)") (class "Default")
      (node (ref "U1") (pin "35") (pinfunction "ADC_VREF_35") (pintype "unspecified+no_connect"))
    )
    (net (code "135") (name "unconnected-(U1-AGND-Pad33)") (class "Default")
      (node (ref "U1") (pin "33") (pinfunction "AGND_33") (pintype "bidirectional+no_connect"))
    )
    (net (code "136") (name "unconnected-(U1-GND-Pad42)") (class "Default")
      (node (ref "U1") (pin "42") (pinfunction "GND_42") (pintype "bidirectional+no_connect"))
    )
    (net (code "137") (name "unconnected-(U1-GPIO2-Pad4)") (class "Default")
      (node (ref "U1") (pin "4") (pinfunction "GPIO2_4") (pintype "bidirectional+no_connect"))
    )
    (net (code "138") (name "unconnected-(U1-GPIO3-Pad5)") (class "Default")
      (node (ref "U1") (pin "5") (pinfunction "GPIO3_5") (pintype "bidirectional+no_connect"))
    )
    (net (code "139") (name "unconnected-(U1-GPIO20-Pad26)") (class "Default")
      (node (ref "U1") (pin "26") (pinfunction "GPIO20_26") (pintype "bidirectional+no_connect"))
    )
    (net (code "140") (name "unconnected-(U1-GPIO22-Pad29)") (class "Default")
      (node (ref "U1") (pin "29") (pinfunction "GPIO22_29") (pintype "bidirectional+no_connect"))
    )
    (net (code "141") (name "unconnected-(U1-GPIO27_ADC1-Pad32)") (class "Default")
      (node (ref "U1") (pin "32") (pinfunction "GPIO27_ADC1_32") (pintype "bidirectional+no_connect"))
    )
    (net (code "142") (name "unconnected-(U1-GPIO28_ADC2-Pad34)") (class "Default")
      (node (ref "U1") (pin "34") (pinfunction "GPIO28_ADC2_34") (pintype "bidirectional+no_connect"))
    )
    (net (code "143") (name "unconnected-(U1-SWCLK-Pad41)") (class "Default")
      (node (ref "U1") (pin "41") (pinfunction "SWCLK_41") (pintype "input+no_connect"))
    )
    (net (code "144") (name "unconnected-(U1-SWDIO-Pad43)") (class "Default")
      (node (ref "U1") (pin "43") (pinfunction "SWDIO_43") (pintype "bidirectional+no_connect"))
    )
    (net (code "145") (name "unconnected-(U2-NC-Pad1)") (class "Default")
      (node (ref "U2") (pin "1") (pinfunction "NC_1") (pintype "unspecified+no_connect"))
    )
    (net (code "146") (name "unconnected-(UX-Pad8)") (class "Default")
      (node (ref "UX") (pin "8") (pinfunction "8_8") (pintype "unspecified+no_connect"))
    )
  )
)
